# FarBreakout.net
KiCad netlist of a schematic drawn in Altium Designer
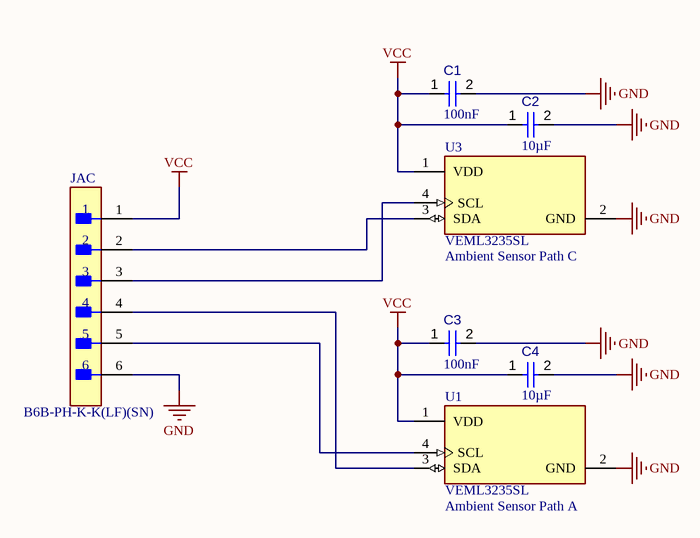
[diagram p0: FarBreakout.SchDoc]

(export (version "E")
  (design (tool "Eeschema 10.0.6"))
  (components
    (comp (ref "C1")
      (value "100nF")
      (footprint "FP-0805-L_2_01_0_2-W_1_25-IPC_B")
      (fields (field (name "Comment") "08051C104K4T2A"))
      (libsource (lib "University of Auckland") (part "CAP-NP-2"))
    )
    (comp (ref "C2")
      (value "10µF")
      (footprint "CAPC0805(2012)145_L")
      (description "Chip Capacitor, 10µF +/-20%, 25V, 0805, Thickness 1.45 mm")
      (fields (field (name "TOLERANCE") "10%") (field (name "Comment") "Capacitor 10µF +/-20% 25V 0805"))
      (libsource (lib "University of Auckland") (part "CAP-NP-2"))
    )
    (comp (ref "C3")
      (value "100nF")
      (footprint "FP-0805-L_2_01_0_2-W_1_25-IPC_B")
      (fields (field (name "Comment") "08051C104K4T2A"))
      (libsource (lib "University of Auckland") (part "CAP-NP-2"))
    )
    (comp (ref "C4")
      (value "10µF")
      (footprint "CAPC0805(2012)145_L")
      (description "Chip Capacitor, 10µF +/-20%, 25V, 0805, Thickness 1.45 mm")
      (fields (field (name "TOLERANCE") "10%") (field (name "Comment") "Capacitor 10µF +/-20% 25V 0805"))
      (libsource (lib "University of Auckland") (part "CAP-NP-2"))
    )
    (comp (ref "JAC")
      (value "B6B-PH-K-K(LF)(SN)")
      (footprint "FP-B6B-PH-K-K_LF_SN-MFG")
      (description "PH Series 6 Position 2 mm Pitch Through Hole Top Entry Shrouded Header")
      (libsource (lib "University of Auckland") (part "f2cb566baf1c37ab5a3b8e90bbeafd6"))
    )
    (comp (ref "U1")
      (value "VEML3235SL")
      (footprint "FP-VEML3235SL-MFG")
      (description "AMBIENT LIGHT SENSOR, IC, SIDE L")
      (libsource (lib "Altium Content Vault") (part "4813be54830ae130d2dc8c8f6975693"))
    )
    (comp (ref "U3")
      (value "VEML3235SL")
      (footprint "FP-VEML3235SL-MFG")
      (description "AMBIENT LIGHT SENSOR, IC, SIDE L")
      (libsource (lib "Altium Content Vault") (part "4813be54830ae130d2dc8c8f6975693"))
    )
  )
  (nets
    (net (code "1") (name "GND") (class "Default")
      (node (ref "C1") (pin "2") (pinfunction "2_2") (pintype "passive"))
      (node (ref "C2") (pin "2") (pinfunction "2_2") (pintype "passive"))
      (node (ref "C3") (pin "2") (pinfunction "2_2") (pintype "passive"))
      (node (ref "C4") (pin "2") (pinfunction "2_2") (pintype "passive"))
      (node (ref "JAC") (pin "6") (pinfunction "6_6") (pintype "passive"))
      (node (ref "U1") (pin "2") (pinfunction "GND_2") (pintype "power_in"))
      (node (ref "U3") (pin "2") (pinfunction "GND_2") (pintype "power_in"))
    )
    (net (code "2") (name "Net-(U1-SCL)") (class "Default")
      (node (ref "JAC") (pin "5") (pinfunction "5_5") (pintype "passive"))
      (node (ref "U1") (pin "4") (pinfunction "SCL_4") (pintype "input"))
    )
    (net (code "3") (name "Net-(U1-SDA)") (class "Default")
      (node (ref "JAC") (pin "4") (pinfunction "4_4") (pintype "passive"))
      (node (ref "U1") (pin "3") (pinfunction "SDA_3") (pintype "bidirectional"))
    )
    (net (code "4") (name "Net-(U3-SCL)") (class "Default")
      (node (ref "JAC") (pin "3") (pinfunction "3_3") (pintype "passive"))
      (node (ref "U3") (pin "4") (pinfunction "SCL_4") (pintype "input"))
    )
    (net (code "5") (name "Net-(U3-SDA)") (class "Default")
      (node (ref "JAC") (pin "2") (pinfunction "2_2") (pintype "passive"))
      (node (ref "U3") (pin "3") (pinfunction "SDA_3") (pintype "bidirectional"))
    )
    (net (code "6") (name "VCC") (class "Default")
      (node (ref "C1") (pin "1") (pinfunction "1_1") (pintype "passive"))
      (node (ref "C2") (pin "1") (pinfunction "1_1") (pintype "passive"))
      (node (ref "C3") (pin "1") (pinfunction "1_1") (pintype "passive"))
      (node (ref "C4") (pin "1") (pinfunction "1_1") (pintype "passive"))
      (node (ref "JAC") (pin "1") (pinfunction "1_1") (pintype "passive"))
      (node (ref "U1") (pin "1") (pinfunction "VDD_1") (pintype "power_in"))
      (node (ref "U3") (pin "1") (pinfunction "VDD_1") (pintype "power_in"))
    )
  )
)
